# rc.net
KiCad netlist of a schematic drawn in EAGLE
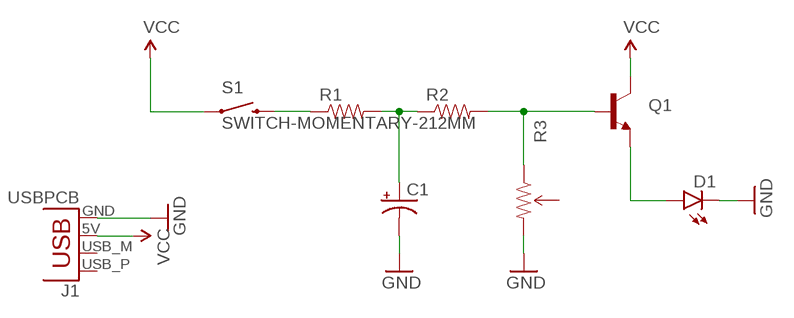
[diagram p0: schematic, sheet 1]

(export (version "E")
  (design (tool "Eeschema 10.0.6"))
  (components
    (comp (ref "C1")
      (value "CAP_POLPTH1")
      (footprint "eagle-import:CPOL-RADIAL-100UF-25V")
      (libsource (lib "eagle-import") (part "CAP_POLPTH1"))
    )
    (comp (ref "D1")
      (value "LED5MM")
      (footprint "eagle-import:LED5MM")
      (libsource (lib "eagle-import") (part "LED5MM"))
    )
    (comp (ref "J1")
      (value "USBPCB")
      (footprint "eagle-import:USB-A-PCB")
      (libsource (lib "eagle-import") (part "USBPCB"))
    )
    (comp (ref "Q1")
      (value "TRANSISTOR_NPNP2N2222A")
      (footprint "eagle-import:TO-92")
      (libsource (lib "eagle-import") (part "TRANSISTOR_NPNP2N2222A"))
    )
    (comp (ref "R1")
      (value "RESISTORPTH-1/6W")
      (footprint "eagle-import:1_6W-RES")
      (libsource (lib "eagle-import") (part "RESISTORPTH-1/6W"))
    )
    (comp (ref "R2")
      (value "RESISTORPTH-1/6W")
      (footprint "eagle-import:1_6W-RES")
      (libsource (lib "eagle-import") (part "RESISTORPTH-1/6W"))
    )
    (comp (ref "R3")
      (value "TRIMPOTPTH")
      (footprint "eagle-import:TRIM_POT_PTH")
      (libsource (lib "eagle-import") (part "TRIMPOTPTH"))
    )
    (comp (ref "S1")
      (value "SWITCH-MOMENTARY-212MM")
      (footprint "eagle-import:TACTILE-PTH-12MM")
      (libsource (lib "eagle-import") (part "SWITCH-MOMENTARY-212MM"))
    )
  )
  (nets
    (net (code "1") (name "GND") (class "Default")
      (node (ref "C1") (pin "2") (pinfunction "-_2") (pintype "passive"))
      (node (ref "D1") (pin "K") (pinfunction "C_K") (pintype "passive"))
      (node (ref "J1") (pin "GND") (pinfunction "GND_GND") (pintype "bidirectional"))
      (node (ref "R3") (pin "3") (pinfunction "CW_3") (pintype "passive"))
    )
    (net (code "2") (name "Net-(C1-+)") (class "Default")
      (node (ref "C1") (pin "1") (pinfunction "+_1") (pintype "passive"))
      (node (ref "R1") (pin "2") (pinfunction "2_2") (pintype "passive"))
      (node (ref "R2") (pin "1") (pinfunction "1_1") (pintype "passive"))
    )
    (net (code "3") (name "Net-(Q1-B)") (class "Default")
      (node (ref "Q1") (pin "2") (pinfunction "B_2") (pintype "passive"))
      (node (ref "R2") (pin "2") (pinfunction "2_2") (pintype "passive"))
      (node (ref "R3") (pin "1") (pinfunction "CCW_1") (pintype "passive"))
    )
    (net (code "4") (name "Net-(Q1-E)") (class "Default")
      (node (ref "D1") (pin "A") (pinfunction "A_A") (pintype "passive"))
      (node (ref "Q1") (pin "3") (pinfunction "E_3") (pintype "passive"))
    )
    (net (code "5") (name "Net-(S1-2)") (class "Default")
      (node (ref "R1") (pin "1") (pinfunction "1_1") (pintype "passive"))
      (node (ref "S1") (pin "3") (pinfunction "2_3") (pintype "passive"))
    )
    (net (code "6") (name "VCC") (class "Default")
      (node (ref "J1") (pin "5V") (pinfunction "VBUS_5V") (pintype "bidirectional"))
      (node (ref "Q1") (pin "1") (pinfunction "C_1") (pintype "passive"))
      (node (ref "S1") (pin "1") (pinfunction "1_1") (pintype "passive"))
    )
    (net (code "7") (name "unconnected-(J1-D+-PadUSB_P)") (class "Default")
      (node (ref "J1") (pin "USB_P") (pinfunction "D+_USB_P") (pintype "bidirectional"))
    )
    (net (code "8") (name "unconnected-(J1-D--PadUSB_M)") (class "Default")
      (node (ref "J1") (pin "USB_M") (pinfunction "D-_USB_M") (pintype "bidirectional"))
    )
    (net (code "9") (name "unconnected-(R3-WIPER-Pad2)") (class "Default")
      (node (ref "R3") (pin "2") (pinfunction "WIPER_2") (pintype "passive"))
    )
  )
)
